# SimpleFlashlight.net
KiCad netlist of a schematic drawn in Altium Designer
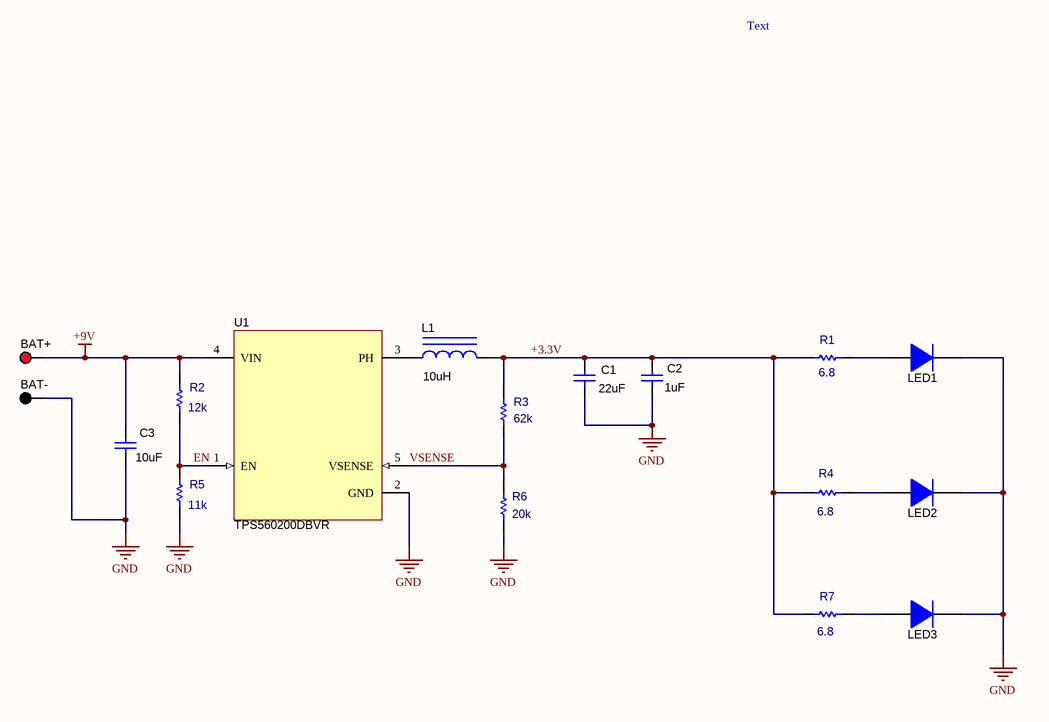
[diagram p0: SimpleFlashlight.SchDoc]

(export (version "E")
  (design (tool "Eeschema 10.0.6"))
  (components
    (comp (ref "BAT+")
      (value "+")
      (footprint "KEYSTONE5000")
      (description "Power connection pad")
      (libsource (lib "SimpleFlashlight") (part "5000"))
    )
    (comp (ref "BAT-")
      (value "-")
      (footprint "KEYSTONE5000")
      (description "Power connection pad")
      (libsource (lib "SimpleFlashlight") (part "5001"))
    )
    (comp (ref "C1")
      (value "22uF")
      (footprint "1206")
      (description "Capacitor ceramic")
      (fields
        (field (name "MANUFACTURER") "MuRata")
        (field (name "MANUFACTURER PART NUMBER") "GRM31CR61C226KE15L")
      )
      (libsource (lib "SimpleFlashlight") (part "Capacitor"))
    )
    (comp (ref "C2")
      (value "1uF")
      (footprint "1206")
      (description "Capacitor ceramic")
      (fields
        (field (name "MANUFACTURER") "MuRata")
        (field (name "MANUFACTURER PART NUMBER") "GRM188R61A105K")
      )
      (libsource (lib "SimpleFlashlight") (part "Capacitor"))
    )
    (comp (ref "C3")
      (value "10uF")
      (footprint "1206")
      (description "Capacitor ceramic")
      (fields
        (field (name "MANUFACTURER") "MuRata")
        (field (name "MANUFACTURER PART NUMBER") "GRM21BR71A106KE51L")
      )
      (libsource (lib "SimpleFlashlight") (part "Capacitor"))
    )
    (comp (ref "L1")
      (value "10uH")
      (footprint "WE-PD_6033")
      (description "Inductor, Unshielded Drum Core, Metal Composite, SMD")
      (fields
        (field (name "MANUFACTURER") "Bourns")
        (field (name "MANUFACTURER PART NUMBER") "SDR0805-100ML")
      )
      (libsource (lib "SimpleFlashlight") (part "Inductor"))
    )
    (comp (ref "LED1")
      (value "4500K")
      (footprint "SimpleFlashlight:LED 2835")
      (description "SMD LED")
      (fields (field (name "MANUFACTURER") "ENLINCA") (field (name "MANUFACTURER PART NUMBER") "None"))
      (libsource (lib "SimpleFlashlight") (part "SMD LED"))
    )
    (comp (ref "LED2")
      (value "4500K")
      (footprint "SimpleFlashlight:LED 2835")
      (description "SMD LED")
      (fields (field (name "MANUFACTURER") "ENLINCA") (field (name "MANUFACTURER PART NUMBER") "None"))
      (libsource (lib "SimpleFlashlight") (part "SMD LED"))
    )
    (comp (ref "LED3")
      (value "4500K")
      (footprint "SimpleFlashlight:LED 2835")
      (description "SMD LED")
      (fields (field (name "MANUFACTURER") "ENLINCA") (field (name "MANUFACTURER PART NUMBER") "None"))
      (libsource (lib "SimpleFlashlight") (part "SMD LED"))
    )
    (comp (ref "R1")
      (value "6.8")
      (footprint "0805_HV")
      (description "Thick Film Chip Resistor")
      (fields
        (field (name "MANUFACTURER PART NUMBER") "RC0805FR-076R8L")
        (field (name "MANUFACTURER") "Yageo")
      )
      (libsource (lib "SimpleFlashlight") (part "Resistor"))
    )
    (comp (ref "R2")
      (value "12k")
      (footprint "0805_HV")
      (description "Thick Film Chip Resistor")
      (fields
        (field (name "MANUFACTURER") "Yageo")
        (field (name "MANUFACTURER PART NUMBER") "RC0805FR-0712KL")
      )
      (libsource (lib "SimpleFlashlight") (part "Resistor"))
    )
    (comp (ref "R3")
      (value "62k")
      (footprint "0805_HV")
      (description "Thick Film Chip Resistor")
      (fields
        (field (name "MANUFACTURER") "Yageo")
        (field (name "MANUFACTURER PART NUMBER") "RC0805FR-0762KL")
      )
      (libsource (lib "SimpleFlashlight") (part "Resistor"))
    )
    (comp (ref "R4")
      (value "6.8")
      (footprint "0805_HV")
      (description "Thick Film Chip Resistor")
      (fields
        (field (name "MANUFACTURER PART NUMBER") "RC0805FR-076R8L")
        (field (name "MANUFACTURER") "Yageo")
      )
      (libsource (lib "SimpleFlashlight") (part "Resistor"))
    )
    (comp (ref "R5")
      (value "11k")
      (footprint "0805_HV")
      (description "Thick Film Chip Resistor")
      (fields
        (field (name "MANUFACTURER") "Yageo")
        (field (name "MANUFACTURER PART NUMBER") "RC0805FR-0711KL")
      )
      (libsource (lib "SimpleFlashlight") (part "Resistor"))
    )
    (comp (ref "R6")
      (value "20k")
      (footprint "0805_HV")
      (description "Thick Film Chip Resistor")
      (fields
        (field (name "MANUFACTURER") "Yageo")
        (field (name "MANUFACTURER PART NUMBER") "RC0805FR-0720KL")
      )
      (libsource (lib "SimpleFlashlight") (part "Resistor"))
    )
    (comp (ref "R7")
      (value "6.8")
      (footprint "0805_HV")
      (description "Thick Film Chip Resistor")
      (fields
        (field (name "MANUFACTURER PART NUMBER") "RC0805FR-076R8L")
        (field (name "MANUFACTURER") "Yageo")
      )
      (libsource (lib "SimpleFlashlight") (part "Resistor"))
    )
    (comp (ref "U1")
      (value "TPS560200DBVR")
      (footprint "SimpleFlashlight:DBV0005A_N")
      (description "4.5V to 18V Input, 500mA Synchronous Step Down SWIFT Converter with Advanced Eco-mode, DBV0005A")
      (fields (field (name "MANUFACTURER") "Texas Instruments"))
      (libsource (lib "SimpleFlashlight") (part "TPS560200DBVR"))
    )
  )
  (nets
    (net (code "1") (name "+9V") (class "Default")
      (node (ref "BAT+") (pin "1") (pintype "passive"))
      (node (ref "C3") (pin "1") (pinfunction "1_1") (pintype "passive"))
      (node (ref "R2") (pin "2") (pinfunction "2_2") (pintype "passive"))
      (node (ref "U1") (pin "4") (pinfunction "VIN_4") (pintype "power_in"))
    )
    (net (code "2") (name "/+3.3V") (class "Default")
      (node (ref "C1") (pin "1") (pinfunction "1_1") (pintype "passive"))
      (node (ref "C2") (pin "1") (pinfunction "1_1") (pintype "passive"))
      (node (ref "L1") (pin "2") (pinfunction "2_2") (pintype "passive"))
      (node (ref "R1") (pin "1") (pinfunction "1_1") (pintype "passive"))
      (node (ref "R3") (pin "2") (pinfunction "2_2") (pintype "passive"))
      (node (ref "R4") (pin "1") (pinfunction "1_1") (pintype "passive"))
      (node (ref "R7") (pin "1") (pinfunction "1_1") (pintype "passive"))
    )
    (net (code "3") (name "/EN") (class "Default")
      (node (ref "R2") (pin "1") (pinfunction "1_1") (pintype "passive"))
      (node (ref "R5") (pin "2") (pinfunction "2_2") (pintype "passive"))
      (node (ref "U1") (pin "1") (pinfunction "EN_1") (pintype "input"))
    )
    (net (code "4") (name "/VSENSE") (class "Default")
      (node (ref "R3") (pin "1") (pinfunction "1_1") (pintype "passive"))
      (node (ref "R6") (pin "2") (pinfunction "2_2") (pintype "passive"))
      (node (ref "U1") (pin "5") (pinfunction "VSENSE_5") (pintype "input"))
    )
    (net (code "5") (name "GND") (class "Default")
      (node (ref "BAT-") (pin "1") (pintype "passive"))
      (node (ref "C1") (pin "2") (pinfunction "2_2") (pintype "passive"))
      (node (ref "C2") (pin "2") (pinfunction "2_2") (pintype "passive"))
      (node (ref "C3") (pin "2") (pinfunction "2_2") (pintype "passive"))
      (node (ref "LED1") (pin "2") (pinfunction "K_2") (pintype "passive"))
      (node (ref "LED2") (pin "2") (pinfunction "K_2") (pintype "passive"))
      (node (ref "LED3") (pin "2") (pinfunction "K_2") (pintype "passive"))
      (node (ref "R5") (pin "1") (pinfunction "1_1") (pintype "passive"))
      (node (ref "R6") (pin "1") (pinfunction "1_1") (pintype "passive"))
      (node (ref "U1") (pin "2") (pinfunction "GND_2") (pintype "power_in"))
    )
    (net (code "6") (name "Net-(LED1-A)") (class "Default")
      (node (ref "LED1") (pin "1") (pinfunction "A_1") (pintype "passive"))
      (node (ref "R1") (pin "2") (pinfunction "2_2") (pintype "passive"))
    )
    (net (code "7") (name "Net-(LED2-A)") (class "Default")
      (node (ref "LED2") (pin "1") (pinfunction "A_1") (pintype "passive"))
      (node (ref "R4") (pin "2") (pinfunction "2_2") (pintype "passive"))
    )
    (net (code "8") (name "Net-(LED3-A)") (class "Default")
      (node (ref "LED3") (pin "1") (pinfunction "A_1") (pintype "passive"))
      (node (ref "R7") (pin "2") (pinfunction "2_2") (pintype "passive"))
    )
    (net (code "9") (name "Net-(U1-PH)") (class "Default")
      (node (ref "L1") (pin "1") (pinfunction "1_1") (pintype "passive"))
      (node (ref "U1") (pin "3") (pinfunction "PH_3") (pintype "power_in"))
    )
  )
)
